# LED.net
KiCad netlist of a schematic drawn in Altium Designer
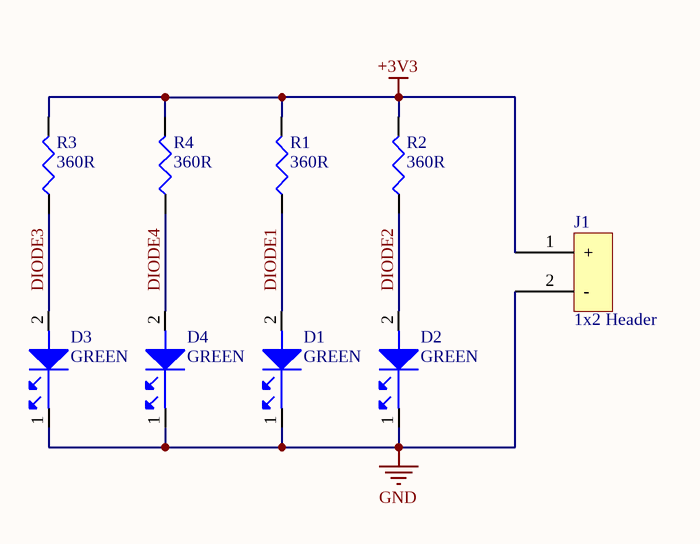
[diagram p0: LED.SchDoc]

(export (version "E")
  (design (tool "Eeschema 10.0.6"))
  (components
    (comp (ref "D1")
      (value "GREEN")
      (footprint "LED0603G")
      (description "Single Color LED")
      (fields
        (field (name "MANUFACTURER") "Visual Communications")
        (field (name "MANUFACTURER PART NUMBER") "LSM0603453V")
      )
      (libsource (lib "LED_SchLib") (part "LSM0603453V"))
    )
    (comp (ref "D2")
      (value "GREEN")
      (footprint "LED0603G")
      (description "Single Color LED")
      (fields
        (field (name "MANUFACTURER") "Visual Communications")
        (field (name "MANUFACTURER PART NUMBER") "LSM0603453V")
      )
      (libsource (lib "LED_SchLib") (part "LSM0603453V"))
    )
    (comp (ref "D3")
      (value "GREEN")
      (footprint "LED0603G")
      (description "Single Color LED")
      (fields
        (field (name "MANUFACTURER") "Visual Communications")
        (field (name "MANUFACTURER PART NUMBER") "LSM0603453V")
      )
      (libsource (lib "LED_SchLib") (part "LSM0603453V"))
    )
    (comp (ref "D4")
      (value "GREEN")
      (footprint "LED0603G")
      (description "Single Color LED")
      (fields
        (field (name "MANUFACTURER") "Visual Communications")
        (field (name "MANUFACTURER PART NUMBER") "LSM0603453V")
      )
      (libsource (lib "LED_SchLib") (part "LSM0603453V"))
    )
    (comp (ref "J1")
      (value "1x2 Header")
      (footprint "HDR1x2")
      (description "CONN HEADER VERT 2POS 2.54MM")
      (fields (field (name "MANUFACTURER") "Molex") (field (name "MANUFACTURER PART NUMBER") "22-27-2021"))
      (libsource (lib "LED_SchLib") (part "22-27-2021"))
    )
    (comp (ref "R1")
      (value "360R")
      (footprint "R0805")
      (description "RES SMD 360 OHM 1% 1/8W 0805")
      (fields
        (field (name "MANUFACTURER") "Yageo")
        (field (name "MANUFACTURER PART NUMBER") "AC0805FR-07360RL")
      )
      (libsource (lib "LED_SchLib") (part "AC0805FR-07360RL"))
    )
    (comp (ref "R2")
      (value "360R")
      (footprint "R0805")
      (description "RES SMD 360 OHM 1% 1/8W 0805")
      (fields
        (field (name "MANUFACTURER") "Yageo")
        (field (name "MANUFACTURER PART NUMBER") "AC0805FR-07360RL")
      )
      (libsource (lib "LED_SchLib") (part "AC0805FR-07360RL"))
    )
    (comp (ref "R3")
      (value "360R")
      (footprint "R0805")
      (description "RES SMD 360 OHM 1% 1/8W 0805")
      (fields
        (field (name "MANUFACTURER") "Yageo")
        (field (name "MANUFACTURER PART NUMBER") "AC0805FR-07360RL")
      )
      (libsource (lib "LED_SchLib") (part "AC0805FR-07360RL"))
    )
    (comp (ref "R4")
      (value "360R")
      (footprint "R0805")
      (description "RES SMD 360 OHM 1% 1/8W 0805")
      (fields
        (field (name "MANUFACTURER") "Yageo")
        (field (name "MANUFACTURER PART NUMBER") "AC0805FR-07360RL")
      )
      (libsource (lib "LED_SchLib") (part "AC0805FR-07360RL"))
    )
  )
  (nets
    (net (code "1") (name "+3V3") (class "Default")
      (node (ref "J1") (pin "1") (pinfunction "+_1") (pintype "passive"))
      (node (ref "R1") (pin "2") (pinfunction "2_2") (pintype "passive"))
      (node (ref "R2") (pin "2") (pinfunction "2_2") (pintype "passive"))
      (node (ref "R3") (pin "2") (pinfunction "2_2") (pintype "passive"))
      (node (ref "R4") (pin "2") (pinfunction "2_2") (pintype "passive"))
    )
    (net (code "2") (name "/DIODE1") (class "Default")
      (node (ref "D1") (pin "2") (pinfunction "2_2") (pintype "passive"))
      (node (ref "R1") (pin "1") (pinfunction "1_1") (pintype "passive"))
    )
    (net (code "3") (name "/DIODE2") (class "Default")
      (node (ref "D2") (pin "2") (pinfunction "2_2") (pintype "passive"))
      (node (ref "R2") (pin "1") (pinfunction "1_1") (pintype "passive"))
    )
    (net (code "4") (name "/DIODE3") (class "Default")
      (node (ref "D3") (pin "2") (pinfunction "2_2") (pintype "passive"))
      (node (ref "R3") (pin "1") (pinfunction "1_1") (pintype "passive"))
    )
    (net (code "5") (name "/DIODE4") (class "Default")
      (node (ref "D4") (pin "2") (pinfunction "2_2") (pintype "passive"))
      (node (ref "R4") (pin "1") (pinfunction "1_1") (pintype "passive"))
    )
    (net (code "6") (name "GND") (class "Default")
      (node (ref "D1") (pin "1") (pinfunction "1_1") (pintype "passive"))
      (node (ref "D2") (pin "1") (pinfunction "1_1") (pintype "passive"))
      (node (ref "D3") (pin "1") (pinfunction "1_1") (pintype "passive"))
      (node (ref "D4") (pin "1") (pinfunction "1_1") (pintype "passive"))
      (node (ref "J1") (pin "2") (pinfunction "-_2") (pintype "passive"))
    )
  )
)
